# XC2C128.net
KiCad netlist of a schematic drawn in Altium Designer
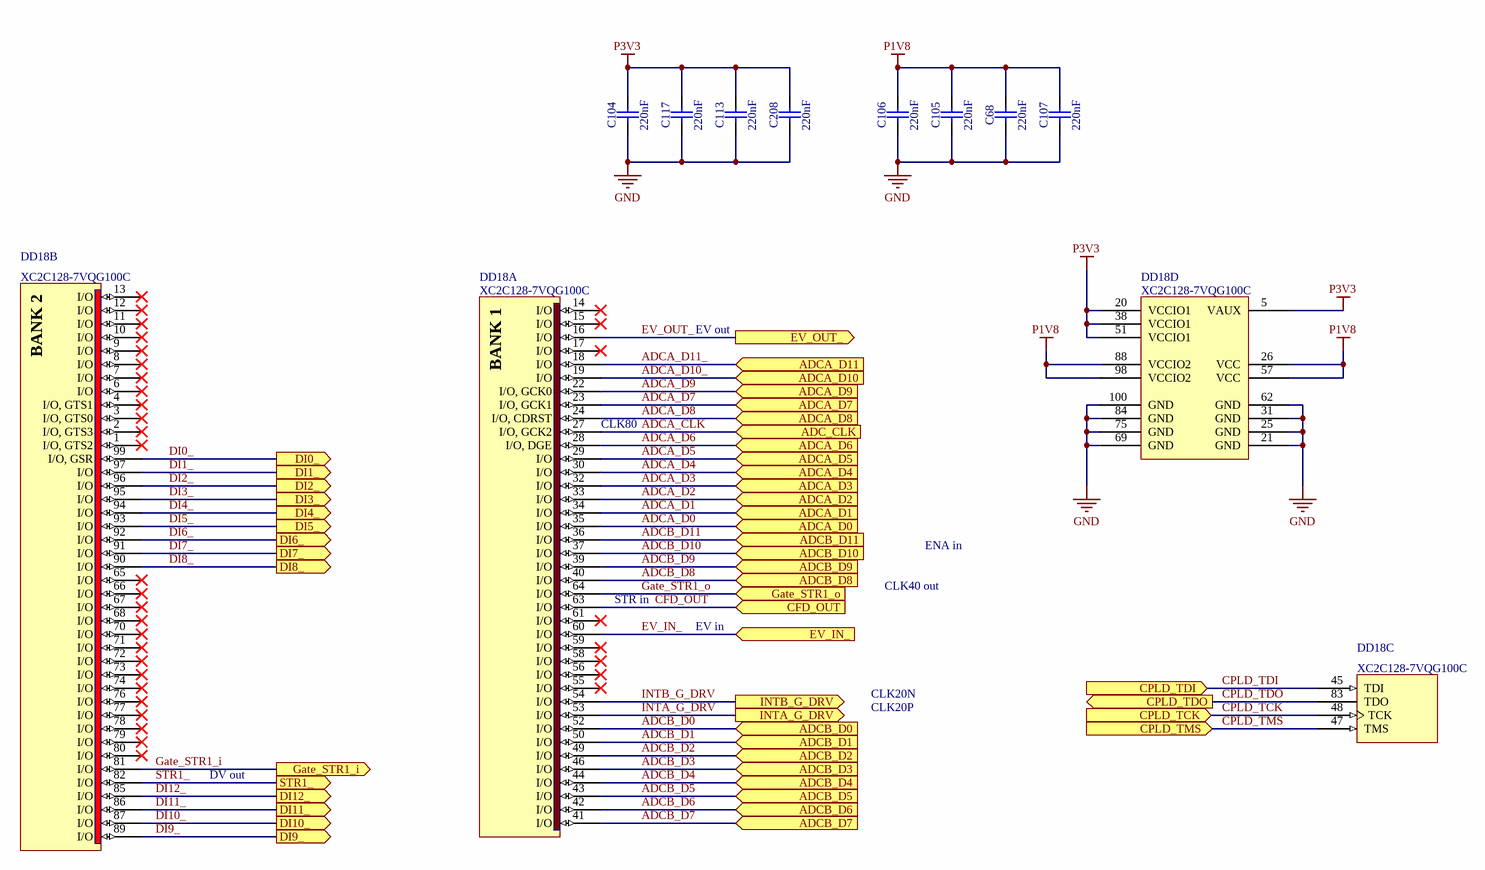
[diagram p0: XC2C128.SchDoc]

(export (version "E")
  (design (tool "Eeschema 10.0.6"))
  (components
    (comp (ref "C68")
      (value "220nF")
      (footprint "CAPC2012X135N")
      (description "Non-polarised capacitor")
      (fields
        (field (name "PART NUMBER") "CC0805_220NF_50V_10%_X7R")
        (field (name "VOLTAGE") "50V")
        (field (name "AUTHOR") "CERN DEM JLC")
      )
      (libsource (lib "Capacitors") (part "Capacitor - non polarized"))
    )
    (comp (ref "C104")
      (value "220nF")
      (footprint "CAPC2012X135N")
      (description "Non-polarised capacitor")
      (fields
        (field (name "PART NUMBER") "CC0805_220NF_50V_10%_X7R")
        (field (name "VOLTAGE") "50V")
        (field (name "AUTHOR") "CERN DEM JLC")
      )
      (libsource (lib "Capacitors") (part "Capacitor - non polarized"))
    )
    (comp (ref "C105")
      (value "220nF")
      (footprint "CAPC2012X135N")
      (description "Non-polarised capacitor")
      (fields
        (field (name "PART NUMBER") "CC0805_220NF_50V_10%_X7R")
        (field (name "VOLTAGE") "50V")
        (field (name "AUTHOR") "CERN DEM JLC")
      )
      (libsource (lib "Capacitors") (part "Capacitor - non polarized"))
    )
    (comp (ref "C106")
      (value "220nF")
      (footprint "CAPC2012X135N")
      (description "Non-polarised capacitor")
      (fields
        (field (name "PART NUMBER") "CC0805_220NF_50V_10%_X7R")
        (field (name "VOLTAGE") "50V")
        (field (name "AUTHOR") "CERN DEM JLC")
      )
      (libsource (lib "Capacitors") (part "Capacitor - non polarized"))
    )
    (comp (ref "C107")
      (value "220nF")
      (footprint "CAPC2012X135N")
      (description "Non-polarised capacitor")
      (fields
        (field (name "PART NUMBER") "CC0805_220NF_50V_10%_X7R")
        (field (name "VOLTAGE") "50V")
        (field (name "AUTHOR") "CERN DEM JLC")
      )
      (libsource (lib "Capacitors") (part "Capacitor - non polarized"))
    )
    (comp (ref "C113")
      (value "220nF")
      (footprint "CAPC2012X135N")
      (description "Non-polarised capacitor")
      (fields
        (field (name "PART NUMBER") "CC0805_220NF_50V_10%_X7R")
        (field (name "VOLTAGE") "50V")
        (field (name "AUTHOR") "CERN DEM JLC")
      )
      (libsource (lib "Capacitors") (part "Capacitor - non polarized"))
    )
    (comp (ref "C117")
      (value "220nF")
      (footprint "CAPC2012X135N")
      (description "Non-polarised capacitor")
      (fields
        (field (name "PART NUMBER") "CC0805_220NF_50V_10%_X7R")
        (field (name "VOLTAGE") "50V")
        (field (name "AUTHOR") "CERN DEM JLC")
      )
      (libsource (lib "Capacitors") (part "Capacitor - non polarized"))
    )
    (comp (ref "C208")
      (value "220nF")
      (footprint "CAPC2012X135N")
      (description "Non-polarised capacitor")
      (fields
        (field (name "PART NUMBER") "CC0805_220NF_50V_10%_X7R")
        (field (name "VOLTAGE") "50V")
        (field (name "AUTHOR") "CERN DEM JLC")
      )
      (libsource (lib "Capacitors") (part "Capacitor - non polarized"))
    )
    (comp (ref "DD18")
      (value "XC2C128-7VQG100C")
      (footprint "QFP50P1600X1600X120-100N")
      (description "CoolRunner-II 1.8V, 128 Macrocell CPLD, 80 User I/Os, 100-Pin VQFP, Commercial Grade, Pb-Free")
      (fields (field (name "MANUFACTURER") "XILINX") (field (name "AUTHOR") "CERN DEM MR"))
      (libsource (lib "ICs And Semiconductors") (part "XC2C128-7VQG100C"))
    )
  )
  (nets
    (net (code "1") (name "/ADCA_CLK") (class "Default")
      (node (ref "DD18") (pin "27") (pinfunction "I/O,_GCK2_27") (pintype "bidirectional"))
    )
    (net (code "2") (name "/ADCA_D0") (class "Default")
      (node (ref "DD18") (pin "35") (pinfunction "I/O_35") (pintype "bidirectional"))
    )
    (net (code "3") (name "/ADCA_D1") (class "Default")
      (node (ref "DD18") (pin "34") (pinfunction "I/O_34") (pintype "bidirectional"))
    )
    (net (code "4") (name "/ADCA_D2") (class "Default")
      (node (ref "DD18") (pin "33") (pinfunction "I/O_33") (pintype "bidirectional"))
    )
    (net (code "5") (name "/ADCA_D3") (class "Default")
      (node (ref "DD18") (pin "32") (pinfunction "I/O_32") (pintype "bidirectional"))
    )
    (net (code "6") (name "/ADCA_D4") (class "Default")
      (node (ref "DD18") (pin "30") (pinfunction "I/O_30") (pintype "bidirectional"))
    )
    (net (code "7") (name "/ADCA_D5") (class "Default")
      (node (ref "DD18") (pin "29") (pinfunction "I/O_29") (pintype "bidirectional"))
    )
    (net (code "8") (name "/ADCA_D6") (class "Default")
      (node (ref "DD18") (pin "28") (pinfunction "I/O,_DGE_28") (pintype "bidirectional"))
    )
    (net (code "9") (name "/ADCA_D7") (class "Default")
      (node (ref "DD18") (pin "23") (pinfunction "I/O,_GCK1_23") (pintype "bidirectional"))
    )
    (net (code "10") (name "/ADCA_D8") (class "Default")
      (node (ref "DD18") (pin "24") (pinfunction "I/O,_CDRST_24") (pintype "bidirectional"))
    )
    (net (code "11") (name "/ADCA_D9") (class "Default")
      (node (ref "DD18") (pin "22") (pinfunction "I/O,_GCK0_22") (pintype "bidirectional"))
    )
    (net (code "12") (name "/ADCA_D10_") (class "Default")
      (node (ref "DD18") (pin "19") (pinfunction "I/O_19") (pintype "bidirectional"))
    )
    (net (code "13") (name "/ADCA_D11_") (class "Default")
      (node (ref "DD18") (pin "18") (pinfunction "I/O_18") (pintype "bidirectional"))
    )
    (net (code "14") (name "/ADCB_D0") (class "Default")
      (node (ref "DD18") (pin "52") (pinfunction "I/O_52") (pintype "bidirectional"))
    )
    (net (code "15") (name "/ADCB_D1") (class "Default")
      (node (ref "DD18") (pin "50") (pinfunction "I/O_50") (pintype "bidirectional"))
    )
    (net (code "16") (name "/ADCB_D2") (class "Default")
      (node (ref "DD18") (pin "49") (pinfunction "I/O_49") (pintype "bidirectional"))
    )
    (net (code "17") (name "/ADCB_D3") (class "Default")
      (node (ref "DD18") (pin "46") (pinfunction "I/O_46") (pintype "bidirectional"))
    )
    (net (code "18") (name "/ADCB_D4") (class "Default")
      (node (ref "DD18") (pin "44") (pinfunction "I/O_44") (pintype "bidirectional"))
    )
    (net (code "19") (name "/ADCB_D5") (class "Default")
      (node (ref "DD18") (pin "43") (pinfunction "I/O_43") (pintype "bidirectional"))
    )
    (net (code "20") (name "/ADCB_D6") (class "Default")
      (node (ref "DD18") (pin "42") (pinfunction "I/O_42") (pintype "bidirectional"))
    )
    (net (code "21") (name "/ADCB_D7") (class "Default")
      (node (ref "DD18") (pin "41") (pinfunction "I/O_41") (pintype "bidirectional"))
    )
    (net (code "22") (name "/ADCB_D8") (class "Default")
      (node (ref "DD18") (pin "40") (pinfunction "I/O_40") (pintype "bidirectional"))
    )
    (net (code "23") (name "/ADCB_D9") (class "Default")
      (node (ref "DD18") (pin "39") (pinfunction "I/O_39") (pintype "bidirectional"))
    )
    (net (code "24") (name "/ADCB_D10") (class "Default")
      (node (ref "DD18") (pin "37") (pinfunction "I/O_37") (pintype "bidirectional"))
    )
    (net (code "25") (name "/ADCB_D11") (class "Default")
      (node (ref "DD18") (pin "36") (pinfunction "I/O_36") (pintype "bidirectional"))
    )
    (net (code "26") (name "/CFD_OUT") (class "Default")
      (node (ref "DD18") (pin "63") (pinfunction "I/O_63") (pintype "bidirectional"))
    )
    (net (code "27") (name "/CPLD_TCK") (class "Default")
      (node (ref "DD18") (pin "48") (pinfunction "TCK_48") (pintype "input"))
    )
    (net (code "28") (name "/CPLD_TDI") (class "Default")
      (node (ref "DD18") (pin "45") (pinfunction "TDI_45") (pintype "input"))
    )
    (net (code "29") (name "/CPLD_TDO") (class "Default")
      (node (ref "DD18") (pin "83") (pinfunction "TDO_83") (pintype "passive"))
    )
    (net (code "30") (name "/CPLD_TMS") (class "Default")
      (node (ref "DD18") (pin "47") (pinfunction "TMS_47") (pintype "input"))
    )
    (net (code "31") (name "/DI0_") (class "Default")
      (node (ref "DD18") (pin "99") (pinfunction "I/O,_GSR_99") (pintype "bidirectional"))
    )
    (net (code "32") (name "/DI1_") (class "Default")
      (node (ref "DD18") (pin "97") (pinfunction "I/O_97") (pintype "bidirectional"))
    )
    (net (code "33") (name "/DI2_") (class "Default")
      (node (ref "DD18") (pin "96") (pinfunction "I/O_96") (pintype "bidirectional"))
    )
    (net (code "34") (name "/DI3_") (class "Default")
      (node (ref "DD18") (pin "95") (pinfunction "I/O_95") (pintype "bidirectional"))
    )
    (net (code "35") (name "/DI4_") (class "Default")
      (node (ref "DD18") (pin "94") (pinfunction "I/O_94") (pintype "bidirectional"))
    )
    (net (code "36") (name "/DI5_") (class "Default")
      (node (ref "DD18") (pin "93") (pinfunction "I/O_93") (pintype "bidirectional"))
    )
    (net (code "37") (name "/DI6_") (class "Default")
      (node (ref "DD18") (pin "92") (pinfunction "I/O_92") (pintype "bidirectional"))
    )
    (net (code "38") (name "/DI7_") (class "Default")
      (node (ref "DD18") (pin "91") (pinfunction "I/O_91") (pintype "bidirectional"))
    )
    (net (code "39") (name "/DI8_") (class "Default")
      (node (ref "DD18") (pin "90") (pinfunction "I/O_90") (pintype "bidirectional"))
    )
    (net (code "40") (name "/DI9_") (class "Default")
      (node (ref "DD18") (pin "89") (pinfunction "I/O_89") (pintype "bidirectional"))
    )
    (net (code "41") (name "/DI10_") (class "Default")
      (node (ref "DD18") (pin "87") (pinfunction "I/O_87") (pintype "bidirectional"))
    )
    (net (code "42") (name "/DI11_") (class "Default")
      (node (ref "DD18") (pin "86") (pinfunction "I/O_86") (pintype "bidirectional"))
    )
    (net (code "43") (name "/DI12_") (class "Default")
      (node (ref "DD18") (pin "85") (pinfunction "I/O_85") (pintype "bidirectional"))
    )
    (net (code "44") (name "/EV_IN_") (class "Default")
      (node (ref "DD18") (pin "60") (pinfunction "I/O_60") (pintype "bidirectional"))
    )
    (net (code "45") (name "/EV_OUT_") (class "Default")
      (node (ref "DD18") (pin "16") (pinfunction "I/O_16") (pintype "bidirectional"))
    )
    (net (code "46") (name "/Gate_STR1_i") (class "Default")
      (node (ref "DD18") (pin "81") (pinfunction "I/O_81") (pintype "bidirectional"))
    )
    (net (code "47") (name "/Gate_STR1_o") (class "Default")
      (node (ref "DD18") (pin "64") (pinfunction "I/O_64") (pintype "bidirectional"))
    )
    (net (code "48") (name "/INTA_G_DRV") (class "Default")
      (node (ref "DD18") (pin "53") (pinfunction "I/O_53") (pintype "bidirectional"))
    )
    (net (code "49") (name "/INTB_G_DRV") (class "Default")
      (node (ref "DD18") (pin "54") (pinfunction "I/O_54") (pintype "bidirectional"))
    )
    (net (code "50") (name "/STR1_") (class "Default")
      (node (ref "DD18") (pin "82") (pinfunction "I/O_82") (pintype "bidirectional"))
    )
    (net (code "51") (name "GND") (class "Default")
      (node (ref "C104") (pin "1") (pinfunction "1_1") (pintype "passive"))
      (node (ref "C105") (pin "1") (pinfunction "1_1") (pintype "passive"))
      (node (ref "C106") (pin "1") (pinfunction "1_1") (pintype "passive"))
      (node (ref "C107") (pin "1") (pinfunction "1_1") (pintype "passive"))
      (node (ref "C113") (pin "1") (pinfunction "1_1") (pintype "passive"))
      (node (ref "C117") (pin "1") (pinfunction "1_1") (pintype "passive"))
      (node (ref "C208") (pin "1") (pinfunction "1_1") (pintype "passive"))
      (node (ref "C68") (pin "1") (pinfunction "1_1") (pintype "passive"))
      (node (ref "DD18") (pin "100") (pinfunction "GND_100") (pintype "power_in"))
      (node (ref "DD18") (pin "21") (pinfunction "GND_21") (pintype "power_in"))
      (node (ref "DD18") (pin "25") (pinfunction "GND_25") (pintype "power_in"))
      (node (ref "DD18") (pin "31") (pinfunction "GND_31") (pintype "power_in"))
      (node (ref "DD18") (pin "62") (pinfunction "GND_62") (pintype "power_in"))
      (node (ref "DD18") (pin "69") (pinfunction "GND_69") (pintype "power_in"))
      (node (ref "DD18") (pin "75") (pinfunction "GND_75") (pintype "power_in"))
      (node (ref "DD18") (pin "84") (pinfunction "GND_84") (pintype "power_in"))
    )
    (net (code "52") (name "P1V8") (class "Default")
      (node (ref "C105") (pin "2") (pinfunction "2_2") (pintype "passive"))
      (node (ref "C106") (pin "2") (pinfunction "2_2") (pintype "passive"))
      (node (ref "C107") (pin "2") (pinfunction "2_2") (pintype "passive"))
      (node (ref "C68") (pin "2") (pinfunction "2_2") (pintype "passive"))
      (node (ref "DD18") (pin "26") (pinfunction "VCC_26") (pintype "power_in"))
      (node (ref "DD18") (pin "57") (pinfunction "VCC_57") (pintype "power_in"))
      (node (ref "DD18") (pin "88") (pinfunction "VCCIO2_88") (pintype "power_in"))
      (node (ref "DD18") (pin "98") (pinfunction "VCCIO2_98") (pintype "power_in"))
    )
    (net (code "53") (name "P3V3") (class "Default")
      (node (ref "C104") (pin "2") (pinfunction "2_2") (pintype "passive"))
      (node (ref "C113") (pin "2") (pinfunction "2_2") (pintype "passive"))
      (node (ref "C117") (pin "2") (pinfunction "2_2") (pintype "passive"))
      (node (ref "C208") (pin "2") (pinfunction "2_2") (pintype "passive"))
      (node (ref "DD18") (pin "20") (pinfunction "VCCIO1_20") (pintype "power_in"))
      (node (ref "DD18") (pin "38") (pinfunction "VCCIO1_38") (pintype "power_in"))
      (node (ref "DD18") (pin "5") (pinfunction "VAUX_5") (pintype "power_in"))
      (node (ref "DD18") (pin "51") (pinfunction "VCCIO1_51") (pintype "power_in"))
    )
    (net (code "54") (name "unconnected-(DD18A-I{slash}O-Pad14)") (class "Default")
      (node (ref "DD18") (pin "14") (pinfunction "I/O_14") (pintype "bidirectional+no_connect"))
    )
    (net (code "55") (name "unconnected-(DD18A-I{slash}O-Pad15)") (class "Default")
      (node (ref "DD18") (pin "15") (pinfunction "I/O_15") (pintype "bidirectional+no_connect"))
    )
    (net (code "56") (name "unconnected-(DD18A-I{slash}O-Pad17)") (class "Default")
      (node (ref "DD18") (pin "17") (pinfunction "I/O_17") (pintype "bidirectional+no_connect"))
    )
    (net (code "57") (name "unconnected-(DD18A-I{slash}O-Pad55)") (class "Default")
      (node (ref "DD18") (pin "55") (pinfunction "I/O_55") (pintype "bidirectional+no_connect"))
    )
    (net (code "58") (name "unconnected-(DD18A-I{slash}O-Pad56)") (class "Default")
      (node (ref "DD18") (pin "56") (pinfunction "I/O_56") (pintype "bidirectional+no_connect"))
    )
    (net (code "59") (name "unconnected-(DD18A-I{slash}O-Pad58)") (class "Default")
      (node (ref "DD18") (pin "58") (pinfunction "I/O_58") (pintype "bidirectional+no_connect"))
    )
    (net (code "60") (name "unconnected-(DD18A-I{slash}O-Pad59)") (class "Default")
      (node (ref "DD18") (pin "59") (pinfunction "I/O_59") (pintype "bidirectional+no_connect"))
    )
    (net (code "61") (name "unconnected-(DD18A-I{slash}O-Pad61)") (class "Default")
      (node (ref "DD18") (pin "61") (pinfunction "I/O_61") (pintype "bidirectional+no_connect"))
    )
    (net (code "62") (name "unconnected-(DD18B-I{slash}O,_GTS0-Pad3)") (class "Default")
      (node (ref "DD18") (pin "3") (pinfunction "I/O,_GTS0_3") (pintype "bidirectional+no_connect"))
    )
    (net (code "63") (name "unconnected-(DD18B-I{slash}O,_GTS1-Pad4)") (class "Default")
      (node (ref "DD18") (pin "4") (pinfunction "I/O,_GTS1_4") (pintype "bidirectional+no_connect"))
    )
    (net (code "64") (name "unconnected-(DD18B-I{slash}O,_GTS2-Pad1)") (class "Default")
      (node (ref "DD18") (pin "1") (pinfunction "I/O,_GTS2_1") (pintype "bidirectional+no_connect"))
    )
    (net (code "65") (name "unconnected-(DD18B-I{slash}O,_GTS3-Pad2)") (class "Default")
      (node (ref "DD18") (pin "2") (pinfunction "I/O,_GTS3_2") (pintype "bidirectional+no_connect"))
    )
    (net (code "66") (name "unconnected-(DD18B-I{slash}O-Pad6)") (class "Default")
      (node (ref "DD18") (pin "6") (pinfunction "I/O_6") (pintype "bidirectional+no_connect"))
    )
    (net (code "67") (name "unconnected-(DD18B-I{slash}O-Pad7)") (class "Default")
      (node (ref "DD18") (pin "7") (pinfunction "I/O_7") (pintype "bidirectional+no_connect"))
    )
    (net (code "68") (name "unconnected-(DD18B-I{slash}O-Pad8)") (class "Default")
      (node (ref "DD18") (pin "8") (pinfunction "I/O_8") (pintype "bidirectional+no_connect"))
    )
    (net (code "69") (name "unconnected-(DD18B-I{slash}O-Pad9)") (class "Default")
      (node (ref "DD18") (pin "9") (pinfunction "I/O_9") (pintype "bidirectional+no_connect"))
    )
    (net (code "70") (name "unconnected-(DD18B-I{slash}O-Pad10)") (class "Default")
      (node (ref "DD18") (pin "10") (pinfunction "I/O_10") (pintype "bidirectional+no_connect"))
    )
    (net (code "71") (name "unconnected-(DD18B-I{slash}O-Pad11)") (class "Default")
      (node (ref "DD18") (pin "11") (pinfunction "I/O_11") (pintype "bidirectional+no_connect"))
    )
    (net (code "72") (name "unconnected-(DD18B-I{slash}O-Pad12)") (class "Default")
      (node (ref "DD18") (pin "12") (pinfunction "I/O_12") (pintype "bidirectional+no_connect"))
    )
    (net (code "73") (name "unconnected-(DD18B-I{slash}O-Pad13)") (class "Default")
      (node (ref "DD18") (pin "13") (pinfunction "I/O_13") (pintype "bidirectional+no_connect"))
    )
    (net (code "74") (name "unconnected-(DD18B-I{slash}O-Pad65)") (class "Default")
      (node (ref "DD18") (pin "65") (pinfunction "I/O_65") (pintype "bidirectional+no_connect"))
    )
    (net (code "75") (name "unconnected-(DD18B-I{slash}O-Pad66)") (class "Default")
      (node (ref "DD18") (pin "66") (pinfunction "I/O_66") (pintype "bidirectional+no_connect"))
    )
    (net (code "76") (name "unconnected-(DD18B-I{slash}O-Pad67)") (class "Default")
      (node (ref "DD18") (pin "67") (pinfunction "I/O_67") (pintype "bidirectional+no_connect"))
    )
    (net (code "77") (name "unconnected-(DD18B-I{slash}O-Pad68)") (class "Default")
      (node (ref "DD18") (pin "68") (pinfunction "I/O_68") (pintype "bidirectional+no_connect"))
    )
    (net (code "78") (name "unconnected-(DD18B-I{slash}O-Pad70)") (class "Default")
      (node (ref "DD18") (pin "70") (pinfunction "I/O_70") (pintype "bidirectional+no_connect"))
    )
    (net (code "79") (name "unconnected-(DD18B-I{slash}O-Pad71)") (class "Default")
      (node (ref "DD18") (pin "71") (pinfunction "I/O_71") (pintype "bidirectional+no_connect"))
    )
    (net (code "80") (name "unconnected-(DD18B-I{slash}O-Pad72)") (class "Default")
      (node (ref "DD18") (pin "72") (pinfunction "I/O_72") (pintype "bidirectional+no_connect"))
    )
    (net (code "81") (name "unconnected-(DD18B-I{slash}O-Pad73)") (class "Default")
      (node (ref "DD18") (pin "73") (pinfunction "I/O_73") (pintype "bidirectional+no_connect"))
    )
    (net (code "82") (name "unconnected-(DD18B-I{slash}O-Pad74)") (class "Default")
      (node (ref "DD18") (pin "74") (pinfunction "I/O_74") (pintype "bidirectional+no_connect"))
    )
    (net (code "83") (name "unconnected-(DD18B-I{slash}O-Pad76)") (class "Default")
      (node (ref "DD18") (pin "76") (pinfunction "I/O_76") (pintype "bidirectional+no_connect"))
    )
    (net (code "84") (name "unconnected-(DD18B-I{slash}O-Pad77)") (class "Default")
      (node (ref "DD18") (pin "77") (pinfunction "I/O_77") (pintype "bidirectional+no_connect"))
    )
    (net (code "85") (name "unconnected-(DD18B-I{slash}O-Pad78)") (class "Default")
      (node (ref "DD18") (pin "78") (pinfunction "I/O_78") (pintype "bidirectional+no_connect"))
    )
    (net (code "86") (name "unconnected-(DD18B-I{slash}O-Pad79)") (class "Default")
      (node (ref "DD18") (pin "79") (pinfunction "I/O_79") (pintype "bidirectional+no_connect"))
    )
    (net (code "87") (name "unconnected-(DD18B-I{slash}O-Pad80)") (class "Default")
      (node (ref "DD18") (pin "80") (pinfunction "I/O_80") (pintype "bidirectional+no_connect"))
    )
  )
)
